# alphanewt_v0_3.net
KiCad netlist of a schematic drawn in EAGLE
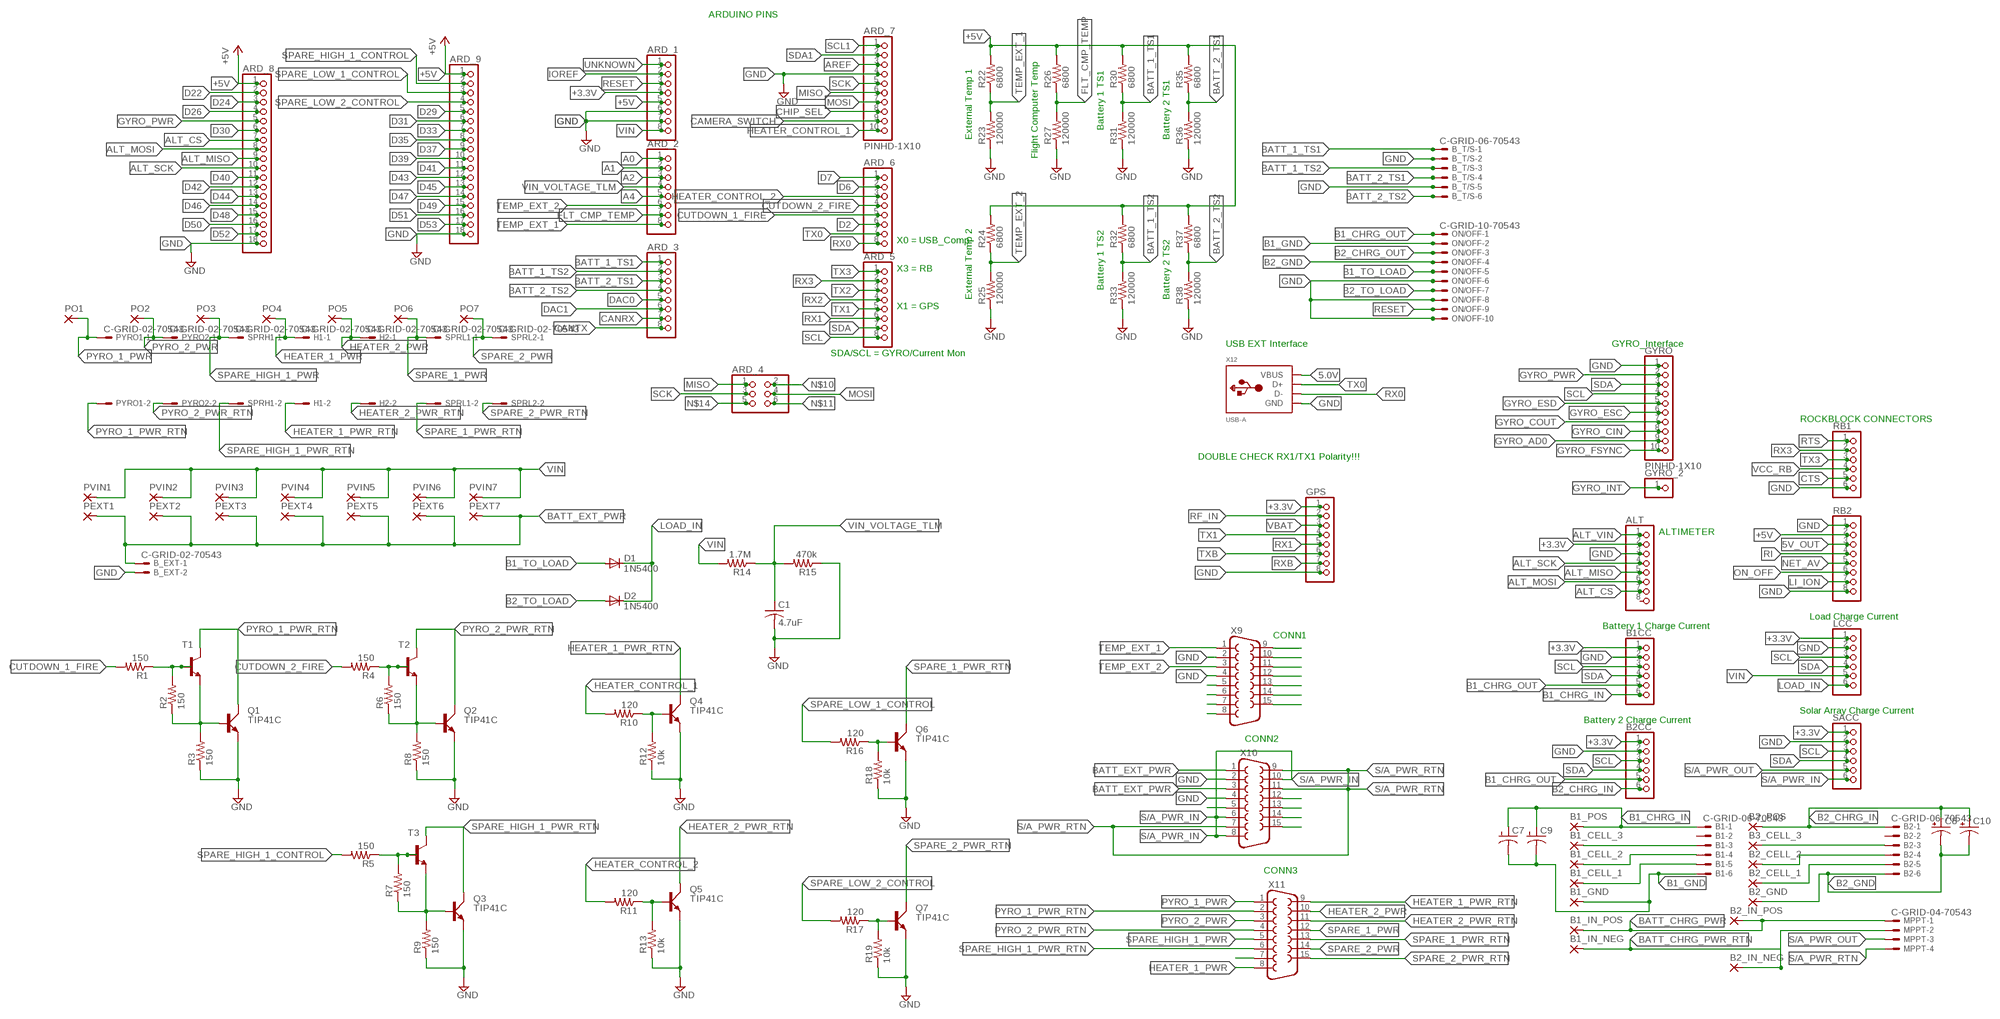
[diagram p0: schematic, sheet 1]

(export (version "E")
  (design (tool "Eeschema 10.0.6"))
  (components
    (comp (ref "ALT")
      (value "PINHD-1X8BIG")
      (footprint "eagle-import:1X08-BIG")
      (libsource (lib "eagle-import") (part "PINHD-1X8BIG"))
    )
    (comp (ref "ARD_1")
      (value "PINHD-1X8BIG")
      (footprint "eagle-import:1X08-BIG")
      (libsource (lib "eagle-import") (part "PINHD-1X8BIG"))
    )
    (comp (ref "ARD_2")
      (value "PINHD-1X8BIG")
      (footprint "eagle-import:1X08-BIG")
      (libsource (lib "eagle-import") (part "PINHD-1X8BIG"))
    )
    (comp (ref "ARD_3")
      (value "PINHD-1X8BIG")
      (footprint "eagle-import:1X08-BIG")
      (libsource (lib "eagle-import") (part "PINHD-1X8BIG"))
    )
    (comp (ref "ARD_4")
      (value "PINHD-2X3")
      (footprint "eagle-import:2X03")
      (libsource (lib "eagle-import") (part "PINHD-2X3"))
    )
    (comp (ref "ARD_5")
      (value "PINHD-1X8BIG")
      (footprint "eagle-import:1X08-BIG")
      (libsource (lib "eagle-import") (part "PINHD-1X8BIG"))
    )
    (comp (ref "ARD_6")
      (value "PINHD-1X8BIG")
      (footprint "eagle-import:1X08-BIG")
      (libsource (lib "eagle-import") (part "PINHD-1X8BIG"))
    )
    (comp (ref "ARD_7")
      (value "PINHD-1X10")
      (footprint "eagle-import:1X10-BIG")
      (libsource (lib "eagle-import") (part "PINHD-1X10"))
    )
    (comp (ref "ARD_8")
      (value "PINHD-1X18-BIG")
      (footprint "eagle-import:1X18-BIG")
      (libsource (lib "eagle-import") (part "PINHD-1X18-BIG"))
    )
    (comp (ref "ARD_9")
      (value "PINHD-1X18-BIG")
      (footprint "eagle-import:1X18-BIG")
      (libsource (lib "eagle-import") (part "PINHD-1X18-BIG"))
    )
    (comp (ref "B1")
      (value "C-GRID-06-70543")
      (footprint "eagle-import:70543-06")
      (libsource (lib "eagle-import") (part "C-GRID-06-70543"))
    )
    (comp (ref "B1CC")
      (value "PINHD-1X6B")
      (footprint "eagle-import:1X06-BIG")
      (libsource (lib "eagle-import") (part "PINHD-1X6B"))
    )
    (comp (ref "B1_CELL_1")
      (value "SMD5")
      (footprint "eagle-import:SMD2,54-5,08")
      (libsource (lib "eagle-import") (part "SMD5"))
    )
    (comp (ref "B1_CELL_2")
      (value "SMD5")
      (footprint "eagle-import:SMD2,54-5,08")
      (libsource (lib "eagle-import") (part "SMD5"))
    )
    (comp (ref "B1_CELL_3")
      (value "SMD5")
      (footprint "eagle-import:SMD2,54-5,08")
      (libsource (lib "eagle-import") (part "SMD5"))
    )
    (comp (ref "B1_GND")
      (value "SMD5")
      (footprint "eagle-import:SMD2,54-5,08")
      (libsource (lib "eagle-import") (part "SMD5"))
    )
    (comp (ref "B1_IN_NEG")
      (value "SMD5")
      (footprint "eagle-import:SMD2,54-5,08")
      (libsource (lib "eagle-import") (part "SMD5"))
    )
    (comp (ref "B1_IN_POS")
      (value "SMD5")
      (footprint "eagle-import:SMD2,54-5,08")
      (libsource (lib "eagle-import") (part "SMD5"))
    )
    (comp (ref "B1_POS")
      (value "SMD5")
      (footprint "eagle-import:SMD2,54-5,08")
      (libsource (lib "eagle-import") (part "SMD5"))
    )
    (comp (ref "B2")
      (value "C-GRID-06-70543")
      (footprint "eagle-import:70543-06")
      (libsource (lib "eagle-import") (part "C-GRID-06-70543"))
    )
    (comp (ref "B2CC")
      (value "PINHD-1X6B")
      (footprint "eagle-import:1X06-BIG")
      (libsource (lib "eagle-import") (part "PINHD-1X6B"))
    )
    (comp (ref "B2_CELL_1")
      (value "SMD5")
      (footprint "eagle-import:SMD2,54-5,08")
      (libsource (lib "eagle-import") (part "SMD5"))
    )
    (comp (ref "B2_CELL_2")
      (value "SMD5")
      (footprint "eagle-import:SMD2,54-5,08")
      (libsource (lib "eagle-import") (part "SMD5"))
    )
    (comp (ref "B2_GND")
      (value "SMD5")
      (footprint "eagle-import:SMD2,54-5,08")
      (libsource (lib "eagle-import") (part "SMD5"))
    )
    (comp (ref "B2_IN_NEG")
      (value "SMD5")
      (footprint "eagle-import:SMD2,54-5,08")
      (libsource (lib "eagle-import") (part "SMD5"))
    )
    (comp (ref "B2_IN_POS")
      (value "SMD5")
      (footprint "eagle-import:SMD2,54-5,08")
      (libsource (lib "eagle-import") (part "SMD5"))
    )
    (comp (ref "B2_POS")
      (value "SMD5")
      (footprint "eagle-import:SMD2,54-5,08")
      (libsource (lib "eagle-import") (part "SMD5"))
    )
    (comp (ref "B3_CELL_3")
      (value "SMD5")
      (footprint "eagle-import:SMD2,54-5,08")
      (libsource (lib "eagle-import") (part "SMD5"))
    )
    (comp (ref "B_EXT")
      (value "C-GRID-02-70543")
      (footprint "eagle-import:70543-02")
      (libsource (lib "eagle-import") (part "C-GRID-02-70543"))
    )
    (comp (ref "B_T/S")
      (value "C-GRID-06-70543")
      (footprint "eagle-import:70543-06")
      (libsource (lib "eagle-import") (part "C-GRID-06-70543"))
    )
    (comp (ref "C1")
      (value "4.7uF")
      (footprint "eagle-import:C0805K")
      (fields (field (name "MPN") "C0805C270J5GACTU"))
      (libsource (lib "eagle-import") (part "C-USC0805K"))
    )
    (comp (ref "C7")
      (value "CPOL-USCT7343")
      (footprint "eagle-import:CT7343")
      (libsource (lib "eagle-import") (part "CPOL-USCT7343"))
    )
    (comp (ref "C8")
      (value "CPOL-USCT7343")
      (footprint "eagle-import:CT7343")
      (libsource (lib "eagle-import") (part "CPOL-USCT7343"))
    )
    (comp (ref "C9")
      (value "CPOL-USCT7343")
      (footprint "eagle-import:CT7343")
      (libsource (lib "eagle-import") (part "CPOL-USCT7343"))
    )
    (comp (ref "C10")
      (value "CPOL-USCT7343")
      (footprint "eagle-import:CT7343")
      (libsource (lib "eagle-import") (part "CPOL-USCT7343"))
    )
    (comp (ref "D1")
      (value "1N5400")
      (footprint "eagle-import:DO201-15")
      (libsource (lib "eagle-import") (part "1N5400"))
    )
    (comp (ref "D2")
      (value "1N5400")
      (footprint "eagle-import:DO201-15")
      (libsource (lib "eagle-import") (part "1N5400"))
    )
    (comp (ref "GPS")
      (value "PINHD-1X8BIG")
      (footprint "eagle-import:1X08-BIG")
      (libsource (lib "eagle-import") (part "PINHD-1X8BIG"))
    )
    (comp (ref "GYRO")
      (value "PINHD-1X10")
      (footprint "eagle-import:1X10-BIG")
      (libsource (lib "eagle-import") (part "PINHD-1X10"))
    )
    (comp (ref "GYRO_2")
      (value "PINHD-1X1")
      (footprint "eagle-import:1X01")
      (libsource (lib "eagle-import") (part "PINHD-1X1"))
    )
    (comp (ref "H1")
      (value "C-GRID-02-70543")
      (footprint "eagle-import:70543-02")
      (libsource (lib "eagle-import") (part "C-GRID-02-70543"))
    )
    (comp (ref "H2")
      (value "C-GRID-02-70543")
      (footprint "eagle-import:70543-02")
      (libsource (lib "eagle-import") (part "C-GRID-02-70543"))
    )
    (comp (ref "LCC")
      (value "PINHD-1X6B")
      (footprint "eagle-import:1X06-BIG")
      (libsource (lib "eagle-import") (part "PINHD-1X6B"))
    )
    (comp (ref "MPPT")
      (value "C-GRID-04-70543")
      (footprint "eagle-import:70543-04")
      (libsource (lib "eagle-import") (part "C-GRID-04-70543"))
    )
    (comp (ref "ON/OFF")
      (value "C-GRID-10-70543")
      (footprint "eagle-import:70543-10")
      (libsource (lib "eagle-import") (part "C-GRID-10-70543"))
    )
    (comp (ref "PEXT1")
      (value "SMD2")
      (footprint "eagle-import:SMD1,27-2,54")
      (libsource (lib "eagle-import") (part "SMD2"))
    )
    (comp (ref "PEXT2")
      (value "SMD2")
      (footprint "eagle-import:SMD1,27-2,54")
      (libsource (lib "eagle-import") (part "SMD2"))
    )
    (comp (ref "PEXT3")
      (value "SMD2")
      (footprint "eagle-import:SMD1,27-2,54")
      (libsource (lib "eagle-import") (part "SMD2"))
    )
    (comp (ref "PEXT4")
      (value "SMD2")
      (footprint "eagle-import:SMD1,27-2,54")
      (libsource (lib "eagle-import") (part "SMD2"))
    )
    (comp (ref "PEXT5")
      (value "SMD2")
      (footprint "eagle-import:SMD1,27-2,54")
      (libsource (lib "eagle-import") (part "SMD2"))
    )
    (comp (ref "PEXT6")
      (value "SMD2")
      (footprint "eagle-import:SMD1,27-2,54")
      (libsource (lib "eagle-import") (part "SMD2"))
    )
    (comp (ref "PEXT7")
      (value "SMD2")
      (footprint "eagle-import:SMD1,27-2,54")
      (libsource (lib "eagle-import") (part "SMD2"))
    )
    (comp (ref "PO1")
      (value "SMD2")
      (footprint "eagle-import:SMD1,27-2,54")
      (libsource (lib "eagle-import") (part "SMD2"))
    )
    (comp (ref "PO2")
      (value "SMD2")
      (footprint "eagle-import:SMD1,27-2,54")
      (libsource (lib "eagle-import") (part "SMD2"))
    )
    (comp (ref "PO3")
      (value "SMD2")
      (footprint "eagle-import:SMD1,27-2,54")
      (libsource (lib "eagle-import") (part "SMD2"))
    )
    (comp (ref "PO4")
      (value "SMD2")
      (footprint "eagle-import:SMD1,27-2,54")
      (libsource (lib "eagle-import") (part "SMD2"))
    )
    (comp (ref "PO5")
      (value "SMD2")
      (footprint "eagle-import:SMD1,27-2,54")
      (libsource (lib "eagle-import") (part "SMD2"))
    )
    (comp (ref "PO6")
      (value "SMD2")
      (footprint "eagle-import:SMD1,27-2,54")
      (libsource (lib "eagle-import") (part "SMD2"))
    )
    (comp (ref "PO7")
      (value "SMD2")
      (footprint "eagle-import:SMD1,27-2,54")
      (libsource (lib "eagle-import") (part "SMD2"))
    )
    (comp (ref "PVIN1")
      (value "SMD2")
      (footprint "eagle-import:SMD1,27-2,54")
      (libsource (lib "eagle-import") (part "SMD2"))
    )
    (comp (ref "PVIN2")
      (value "SMD2")
      (footprint "eagle-import:SMD1,27-2,54")
      (libsource (lib "eagle-import") (part "SMD2"))
    )
    (comp (ref "PVIN3")
      (value "SMD2")
      (footprint "eagle-import:SMD1,27-2,54")
      (libsource (lib "eagle-import") (part "SMD2"))
    )
    (comp (ref "PVIN4")
      (value "SMD2")
      (footprint "eagle-import:SMD1,27-2,54")
      (libsource (lib "eagle-import") (part "SMD2"))
    )
    (comp (ref "PVIN5")
      (value "SMD2")
      (footprint "eagle-import:SMD1,27-2,54")
      (libsource (lib "eagle-import") (part "SMD2"))
    )
    (comp (ref "PVIN6")
      (value "SMD2")
      (footprint "eagle-import:SMD1,27-2,54")
      (libsource (lib "eagle-import") (part "SMD2"))
    )
    (comp (ref "PVIN7")
      (value "SMD2")
      (footprint "eagle-import:SMD1,27-2,54")
      (libsource (lib "eagle-import") (part "SMD2"))
    )
    (comp (ref "PYRO1")
      (value "C-GRID-02-70543")
      (footprint "eagle-import:70543-02")
      (libsource (lib "eagle-import") (part "C-GRID-02-70543"))
    )
    (comp (ref "PYRO2")
      (value "C-GRID-02-70543")
      (footprint "eagle-import:70543-02")
      (libsource (lib "eagle-import") (part "C-GRID-02-70543"))
    )
    (comp (ref "Q1")
      (value "TIP41C")
      (footprint "eagle-import:TO220AV")
      (libsource (lib "eagle-import") (part "TIP41C"))
    )
    (comp (ref "Q2")
      (value "TIP41C")
      (footprint "eagle-import:TO220AV")
      (libsource (lib "eagle-import") (part "TIP41C"))
    )
    (comp (ref "Q3")
      (value "TIP41C")
      (footprint "eagle-import:TO220AV")
      (libsource (lib "eagle-import") (part "TIP41C"))
    )
    (comp (ref "Q4")
      (value "TIP41C")
      (footprint "eagle-import:TO220AV")
      (libsource (lib "eagle-import") (part "TIP41C"))
    )
    (comp (ref "Q5")
      (value "TIP41C")
      (footprint "eagle-import:TO220AV")
      (libsource (lib "eagle-import") (part "TIP41C"))
    )
    (comp (ref "Q6")
      (value "TIP41C")
      (footprint "eagle-import:TO220AV")
      (libsource (lib "eagle-import") (part "TIP41C"))
    )
    (comp (ref "Q7")
      (value "TIP41C")
      (footprint "eagle-import:TO220AV")
      (libsource (lib "eagle-import") (part "TIP41C"))
    )
    (comp (ref "R1")
      (value "150")
      (footprint "eagle-import:R0805")
      (fields (field (name "MF") "VISHAY/DALE") (field (name "MPN") "CRCW120633R2FKEA"))
      (libsource (lib "eagle-import") (part "R-US_R0805"))
    )
    (comp (ref "R2")
      (value "150")
      (footprint "eagle-import:R0805")
      (fields (field (name "MF") "VISHAY/DALE") (field (name "MPN") "CRCW120633R2FKEA"))
      (libsource (lib "eagle-import") (part "R-US_R0805"))
    )
    (comp (ref "R3")
      (value "150")
      (footprint "eagle-import:R0805")
      (fields (field (name "MF") "VISHAY/DALE") (field (name "MPN") "CRCW120633R2FKEA"))
      (libsource (lib "eagle-import") (part "R-US_R0805"))
    )
    (comp (ref "R4")
      (value "150")
      (footprint "eagle-import:R0805")
      (fields (field (name "MF") "VISHAY/DALE") (field (name "MPN") "CRCW120633R2FKEA"))
      (libsource (lib "eagle-import") (part "R-US_R0805"))
    )
    (comp (ref "R5")
      (value "150")
      (footprint "eagle-import:R0805")
      (fields (field (name "MF") "VISHAY/DALE") (field (name "MPN") "CRCW120633R2FKEA"))
      (libsource (lib "eagle-import") (part "R-US_R0805"))
    )
    (comp (ref "R6")
      (value "150")
      (footprint "eagle-import:R0805")
      (fields (field (name "MF") "VISHAY/DALE") (field (name "MPN") "CRCW120633R2FKEA"))
      (libsource (lib "eagle-import") (part "R-US_R0805"))
    )
    (comp (ref "R7")
      (value "150")
      (footprint "eagle-import:R0805")
      (fields (field (name "MF") "VISHAY/DALE") (field (name "MPN") "CRCW120633R2FKEA"))
      (libsource (lib "eagle-import") (part "R-US_R0805"))
    )
    (comp (ref "R8")
      (value "150")
      (footprint "eagle-import:R0805")
      (fields (field (name "MF") "VISHAY/DALE") (field (name "MPN") "CRCW120633R2FKEA"))
      (libsource (lib "eagle-import") (part "R-US_R0805"))
    )
    (comp (ref "R9")
      (value "150")
      (footprint "eagle-import:R0805")
      (fields (field (name "MF") "VISHAY/DALE") (field (name "MPN") "CRCW120633R2FKEA"))
      (libsource (lib "eagle-import") (part "R-US_R0805"))
    )
    (comp (ref "R10")
      (value "120")
      (footprint "eagle-import:R0805")
      (fields (field (name "MF") "VISHAY/DALE") (field (name "MPN") "CRCW120633R2FKEA"))
      (libsource (lib "eagle-import") (part "R-US_R0805"))
    )
    (comp (ref "R11")
      (value "120")
      (footprint "eagle-import:R0805")
      (fields (field (name "MF") "VISHAY/DALE") (field (name "MPN") "CRCW120633R2FKEA"))
      (libsource (lib "eagle-import") (part "R-US_R0805"))
    )
    (comp (ref "R12")
      (value "10k")
      (footprint "eagle-import:R0805")
      (fields (field (name "MF") "VISHAY/DALE") (field (name "MPN") "CRCW120633R2FKEA"))
      (libsource (lib "eagle-import") (part "R-US_R0805"))
    )
    (comp (ref "R13")
      (value "10k")
      (footprint "eagle-import:R0805")
      (fields (field (name "MF") "VISHAY/DALE") (field (name "MPN") "CRCW120633R2FKEA"))
      (libsource (lib "eagle-import") (part "R-US_R0805"))
    )
    (comp (ref "R14")
      (value "1.7M")
      (footprint "eagle-import:R0805")
      (fields (field (name "MF") "VISHAY/DALE") (field (name "MPN") "CRCW120633R2FKEA"))
      (libsource (lib "eagle-import") (part "R-US_R0805"))
    )
    (comp (ref "R15")
      (value "470k")
      (footprint "eagle-import:R0805")
      (fields (field (name "MF") "VISHAY/DALE") (field (name "MPN") "CRCW120633R2FKEA"))
      (libsource (lib "eagle-import") (part "R-US_R0805"))
    )
    (comp (ref "R16")
      (value "120")
      (footprint "eagle-import:R0805")
      (fields (field (name "MF") "VISHAY/DALE") (field (name "MPN") "CRCW120633R2FKEA"))
      (libsource (lib "eagle-import") (part "R-US_R0805"))
    )
    (comp (ref "R17")
      (value "120")
      (footprint "eagle-import:R0805")
      (fields (field (name "MF") "VISHAY/DALE") (field (name "MPN") "CRCW120633R2FKEA"))
      (libsource (lib "eagle-import") (part "R-US_R0805"))
    )
    (comp (ref "R18")
      (value "10k")
      (footprint "eagle-import:R0805")
      (fields (field (name "MF") "VISHAY/DALE") (field (name "MPN") "CRCW120633R2FKEA"))
      (libsource (lib "eagle-import") (part "R-US_R0805"))
    )
    (comp (ref "R19")
      (value "10k")
      (footprint "eagle-import:R0805")
      (fields (field (name "MF") "VISHAY/DALE") (field (name "MPN") "CRCW120633R2FKEA"))
      (libsource (lib "eagle-import") (part "R-US_R0805"))
    )
    (comp (ref "R22")
      (value "6800")
      (footprint "eagle-import:R0805")
      (fields (field (name "MF") "VISHAY/DALE") (field (name "MPN") "CRCW120633R2FKEA"))
      (libsource (lib "eagle-import") (part "R-US_R0805"))
    )
    (comp (ref "R23")
      (value "120000")
      (footprint "eagle-import:R0805")
      (fields (field (name "MF") "VISHAY/DALE") (field (name "MPN") "CRCW120633R2FKEA"))
      (libsource (lib "eagle-import") (part "R-US_R0805"))
    )
    (comp (ref "R24")
      (value "6800")
      (footprint "eagle-import:R0805")
      (fields (field (name "MF") "VISHAY/DALE") (field (name "MPN") "CRCW120633R2FKEA"))
      (libsource (lib "eagle-import") (part "R-US_R0805"))
    )
    (comp (ref "R25")
      (value "120000")
      (footprint "eagle-import:R0805")
      (fields (field (name "MF") "VISHAY/DALE") (field (name "MPN") "CRCW120633R2FKEA"))
      (libsource (lib "eagle-import") (part "R-US_R0805"))
    )
    (comp (ref "R26")
      (value "6800")
      (footprint "eagle-import:R0805")
      (fields (field (name "MF") "VISHAY/DALE") (field (name "MPN") "CRCW120633R2FKEA"))
      (libsource (lib "eagle-import") (part "R-US_R0805"))
    )
    (comp (ref "R27")
      (value "120000")
      (footprint "eagle-import:R0805")
      (fields (field (name "MF") "VISHAY/DALE") (field (name "MPN") "CRCW120633R2FKEA"))
      (libsource (lib "eagle-import") (part "R-US_R0805"))
    )
    (comp (ref "R30")
      (value "6800")
      (footprint "eagle-import:R0805")
      (fields (field (name "MF") "VISHAY/DALE") (field (name "MPN") "CRCW120633R2FKEA"))
      (libsource (lib "eagle-import") (part "R-US_R0805"))
    )
    (comp (ref "R31")
      (value "120000")
      (footprint "eagle-import:R0805")
      (fields (field (name "MF") "VISHAY/DALE") (field (name "MPN") "CRCW120633R2FKEA"))
      (libsource (lib "eagle-import") (part "R-US_R0805"))
    )
    (comp (ref "R32")
      (value "6800")
      (footprint "eagle-import:R0805")
      (fields (field (name "MF") "VISHAY/DALE") (field (name "MPN") "CRCW120633R2FKEA"))
      (libsource (lib "eagle-import") (part "R-US_R0805"))
    )
    (comp (ref "R33")
      (value "120000")
      (footprint "eagle-import:R0805")
      (fields (field (name "MF") "VISHAY/DALE") (field (name "MPN") "CRCW120633R2FKEA"))
      (libsource (lib "eagle-import") (part "R-US_R0805"))
    )
    (comp (ref "R35")
      (value "6800")
      (footprint "eagle-import:R0805")
      (fields (field (name "MF") "VISHAY/DALE") (field (name "MPN") "CRCW120633R2FKEA"))
      (libsource (lib "eagle-import") (part "R-US_R0805"))
    )
    (comp (ref "R36")
      (value "120000")
      (footprint "eagle-import:R0805")
      (fields (field (name "MF") "VISHAY/DALE") (field (name "MPN") "CRCW120633R2FKEA"))
      (libsource (lib "eagle-import") (part "R-US_R0805"))
    )
    (comp (ref "R37")
      (value "6800")
      (footprint "eagle-import:R0805")
      (fields (field (name "MF") "VISHAY/DALE") (field (name "MPN") "CRCW120633R2FKEA"))
      (libsource (lib "eagle-import") (part "R-US_R0805"))
    )
    (comp (ref "R38")
      (value "120000")
      (footprint "eagle-import:R0805")
      (fields (field (name "MF") "VISHAY/DALE") (field (name "MPN") "CRCW120633R2FKEA"))
      (libsource (lib "eagle-import") (part "R-US_R0805"))
    )
    (comp (ref "RB1")
      (value "PINHD-1X6CB")
      (footprint "eagle-import:1X06-CLEANBIG")
      (libsource (lib "eagle-import") (part "PINHD-1X6CB"))
    )
    (comp (ref "RB2")
      (value "PINHD-1X8BIG")
      (footprint "eagle-import:1X08-BIG")
      (libsource (lib "eagle-import") (part "PINHD-1X8BIG"))
    )
    (comp (ref "SACC")
      (value "PINHD-1X6B")
      (footprint "eagle-import:1X06-BIG")
      (libsource (lib "eagle-import") (part "PINHD-1X6B"))
    )
    (comp (ref "SPRH1")
      (value "C-GRID-02-70543")
      (footprint "eagle-import:70543-02")
      (libsource (lib "eagle-import") (part "C-GRID-02-70543"))
    )
    (comp (ref "SPRL1")
      (value "C-GRID-02-70543")
      (footprint "eagle-import:70543-02")
      (libsource (lib "eagle-import") (part "C-GRID-02-70543"))
    )
    (comp (ref "SPRL2")
      (value "C-GRID-02-70543")
      (footprint "eagle-import:70543-02")
      (libsource (lib "eagle-import") (part "C-GRID-02-70543"))
    )
    (comp (ref "T1")
      (value "2N3904")
      (footprint "eagle-import:TO92")
      (libsource (lib "eagle-import") (part "2N3904"))
    )
    (comp (ref "T2")
      (value "2N3904")
      (footprint "eagle-import:TO92")
      (libsource (lib "eagle-import") (part "2N3904"))
    )
    (comp (ref "T3")
      (value "2N3904")
      (footprint "eagle-import:TO92")
      (libsource (lib "eagle-import") (part "2N3904"))
    )
    (comp (ref "X9")
      (value "F15HP")
      (footprint "eagle-import:F15HP")
      (libsource (lib "eagle-import") (part "F15HP"))
    )
    (comp (ref "X10")
      (value "F15HP")
      (footprint "eagle-import:F15HP")
      (libsource (lib "eagle-import") (part "F15HP"))
    )
    (comp (ref "X11")
      (value "F15HP")
      (footprint "eagle-import:F15HP")
      (libsource (lib "eagle-import") (part "F15HP"))
    )
    (comp (ref "X12")
      (value "USB-A")
      (footprint "eagle-import:MOLEX_480371000")
      (libsource (lib "eagle-import") (part "USB-A"))
    )
  )
  (nets
    (net (code "1") (name "+3.3V") (class "Default")
      (node (ref "ALT") (pin "2") (pinfunction "2_2") (pintype "passive"))
      (node (ref "ARD_1") (pin "4") (pinfunction "4_4") (pintype "passive"))
      (node (ref "B1CC") (pin "1") (pinfunction "1_1") (pintype "passive"))
      (node (ref "B2CC") (pin "1") (pinfunction "1_1") (pintype "passive"))
      (node (ref "GPS") (pin "1") (pinfunction "1_1") (pintype "passive"))
      (node (ref "LCC") (pin "1") (pinfunction "1_1") (pintype "passive"))
      (node (ref "SACC") (pin "1") (pinfunction "1_1") (pintype "passive"))
    )
    (net (code "2") (name "+5V") (class "Default")
      (node (ref "ARD_1") (pin "5") (pinfunction "5_5") (pintype "passive"))
      (node (ref "ARD_8") (pin "1") (pinfunction "1_1") (pintype "passive"))
      (node (ref "ARD_9") (pin "1") (pinfunction "1_1") (pintype "passive"))
      (node (ref "R22") (pin "2") (pinfunction "2_2") (pintype "passive"))
      (node (ref "R24") (pin "2") (pinfunction "2_2") (pintype "passive"))
      (node (ref "R26") (pin "2") (pinfunction "2_2") (pintype "passive"))
      (node (ref "R30") (pin "2") (pinfunction "2_2") (pintype "passive"))
      (node (ref "R32") (pin "2") (pinfunction "2_2") (pintype "passive"))
      (node (ref "R35") (pin "2") (pinfunction "2_2") (pintype "passive"))
      (node (ref "R37") (pin "2") (pinfunction "2_2") (pintype "passive"))
      (node (ref "RB2") (pin "2") (pinfunction "2_2") (pintype "passive"))
    )
    (net (code "3") (name "5.0V") (class "Default")
      (node (ref "X12") (pin "1") (pinfunction "VBUS_1") (pintype "power_in"))
    )
    (net (code "4") (name "5V_OUT") (class "Default")
      (node (ref "RB2") (pin "3") (pinfunction "3_3") (pintype "passive"))
    )
    (net (code "5") (name "A0") (class "Default")
      (node (ref "ARD_2") (pin "1") (pinfunction "1_1") (pintype "passive"))
    )
    (net (code "6") (name "A1") (class "Default")
      (node (ref "ARD_2") (pin "2") (pinfunction "2_2") (pintype "passive"))
    )
    (net (code "7") (name "A2") (class "Default")
      (node (ref "ARD_2") (pin "3") (pinfunction "3_3") (pintype "passive"))
    )
    (net (code "8") (name "A4") (class "Default")
      (node (ref "ARD_2") (pin "5") (pinfunction "5_5") (pintype "passive"))
    )
    (net (code "9") (name "ALT_CS") (class "Default")
      (node (ref "ALT") (pin "7") (pinfunction "7_7") (pintype "passive"))
      (node (ref "ARD_8") (pin "7") (pinfunction "7_7") (pintype "passive"))
    )
    (net (code "10") (name "ALT_MISO") (class "Default")
      (node (ref "ALT") (pin "5") (pinfunction "5_5") (pintype "passive"))
      (node (ref "ARD_8") (pin "9") (pinfunction "9_9") (pintype "passive"))
    )
    (net (code "11") (name "ALT_MOSI") (class "Default")
      (node (ref "ALT") (pin "6") (pinfunction "6_6") (pintype "passive"))
      (node (ref "ARD_8") (pin "8") (pinfunction "8_8") (pintype "passive"))
    )
    (net (code "12") (name "ALT_SCK") (class "Default")
      (node (ref "ALT") (pin "4") (pinfunction "4_4") (pintype "passive"))
      (node (ref "ARD_8") (pin "10") (pinfunction "10_10") (pintype "passive"))
    )
    (net (code "13") (name "ALT_VIN") (class "Default")
      (node (ref "ALT") (pin "1") (pinfunction "1_1") (pintype "passive"))
    )
    (net (code "14") (name "AREF") (class "Default")
      (node (ref "ARD_7") (pin "3") (pinfunction "3_3") (pintype "passive"))
    )
    (net (code "15") (name "B1_CHRG_IN") (class "Default")
      (node (ref "B1") (pin "1") (pinfunction "S_1") (pintype "passive"))
      (node (ref "B1CC") (pin "6") (pinfunction "6_6") (pintype "passive"))
      (node (ref "B1_POS") (pin "1") (pinfunction "P_1") (pintype "passive"))
      (node (ref "C7") (pin "+") (pinfunction "+_+") (pintype "passive"))
      (node (ref "C9") (pin "+") (pinfunction "+_+") (pintype "passive"))
    )
    (net (code "16") (name "B1_CHRG_OUT") (class "Default")
      (node (ref "B1CC") (pin "5") (pinfunction "5_5") (pintype "passive"))
      (node (ref "B2CC") (pin "5") (pinfunction "5_5") (pintype "passive"))
      (node (ref "ON/OFF") (pin "1") (pinfunction "S_1") (pintype "passive"))
    )
    (net (code "17") (name "B1_GND") (class "Default")
      (node (ref "B1") (pin "6") (pinfunction "S_6") (pintype "passive"))
      (node (ref "B1_GND") (pin "1") (pinfunction "P_1") (pintype "passive"))
      (node (ref "C7") (pin "-") (pinfunction "-_-") (pintype "passive"))
      (node (ref "C9") (pin "-") (pinfunction "-_-") (pintype "passive"))
      (node (ref "ON/OFF") (pin "2") (pinfunction "S_2") (pintype "passive"))
    )
    (net (code "18") (name "B1_TO_LOAD") (class "Default")
      (node (ref "D1") (pin "A") (pinfunction "A_A") (pintype "passive"))
      (node (ref "ON/OFF") (pin "5") (pinfunction "S_5") (pintype "passive"))
    )
    (net (code "19") (name "B2_CHRG_IN") (class "Default")
      (node (ref "B2") (pin "1") (pinfunction "S_1") (pintype "passive"))
      (node (ref "B2CC") (pin "6") (pinfunction "6_6") (pintype "passive"))
      (node (ref "B2_POS") (pin "1") (pinfunction "P_1") (pintype "passive"))
      (node (ref "C10") (pin "+") (pinfunction "+_+") (pintype "passive"))
      (node (ref "C8") (pin "+") (pinfunction "+_+") (pintype "passive"))
    )
    (net (code "20") (name "B2_CHRG_OUT") (class "Default")
      (node (ref "ON/OFF") (pin "3") (pinfunction "S_3") (pintype "passive"))
    )
    (net (code "21") (name "B2_GND") (class "Default")
      (node (ref "B2") (pin "6") (pinfunction "S_6") (pintype "passive"))
      (node (ref "B2_GND") (pin "1") (pinfunction "P_1") (pintype "passive"))
      (node (ref "C10") (pin "-") (pinfunction "-_-") (pintype "passive"))
      (node (ref "C8") (pin "-") (pinfunction "-_-") (pintype "passive"))
      (node (ref "ON/OFF") (pin "4") (pinfunction "S_4") (pintype "passive"))
    )
    (net (code "22") (name "B2_TO_LOAD") (class "Default")
      (node (ref "D2") (pin "A") (pinfunction "A_A") (pintype "passive"))
      (node (ref "ON/OFF") (pin "7") (pinfunction "S_7") (pintype "passive"))
    )
    (net (code "23") (name "BATT_1_TS1") (class "Default")
      (node (ref "ARD_3") (pin "1") (pinfunction "1_1") (pintype "passive"))
      (node (ref "B_T/S") (pin "1") (pinfunction "S_1") (pintype "passive"))
      (node (ref "R30") (pin "1") (pinfunction "1_1") (pintype "passive"))
      (node (ref "R31") (pin "2") (pinfunction "2_2") (pintype "passive"))
    )
    (net (code "24") (name "BATT_1_TS2") (class "Default")
      (node (ref "ARD_3") (pin "2") (pinfunction "2_2") (pintype "passive"))
      (node (ref "B_T/S") (pin "3") (pinfunction "S_3") (pintype "passive"))
      (node (ref "R32") (pin "1") (pinfunction "1_1") (pintype "passive"))
      (node (ref "R33") (pin "2") (pinfunction "2_2") (pintype "passive"))
    )
    (net (code "25") (name "BATT_2_TS1") (class "Default")
      (node (ref "ARD_3") (pin "3") (pinfunction "3_3") (pintype "passive"))
      (node (ref "B_T/S") (pin "4") (pinfunction "S_4") (pintype "passive"))
      (node (ref "R35") (pin "1") (pinfunction "1_1") (pintype "passive"))
      (node (ref "R36") (pin "2") (pinfunction "2_2") (pintype "passive"))
    )
    (net (code "26") (name "BATT_2_TS2") (class "Default")
      (node (ref "ARD_3") (pin "4") (pinfunction "4_4") (pintype "passive"))
      (node (ref "B_T/S") (pin "6") (pinfunction "S_6") (pintype "passive"))
      (node (ref "R37") (pin "1") (pinfunction "1_1") (pintype "passive"))
      (node (ref "R38") (pin "2") (pinfunction "2_2") (pintype "passive"))
    )
    (net (code "27") (name "BATT_CHRG_PWR") (class "Default")
      (node (ref "B1_IN_POS") (pin "1") (pinfunction "P_1") (pintype "passive"))
      (node (ref "B2_IN_POS") (pin "1") (pinfunction "P_1") (pintype "passive"))
      (node (ref "MPPT") (pin "1") (pinfunction "S_1") (pintype "passive"))
    )
    (net (code "28") (name "BATT_CHRG_PWR_RTN") (class "Default")
      (node (ref "B1_IN_NEG") (pin "1") (pinfunction "P_1") (pintype "passive"))
      (node (ref "B2_IN_NEG") (pin "1") (pinfunction "P_1") (pintype "passive"))
      (node (ref "MPPT") (pin "2") (pinfunction "S_2") (pintype "passive"))
    )
    (net (code "29") (name "BATT_EXT_PWR") (class "Default")
      (node (ref "B_EXT") (pin "1") (pinfunction "S_1") (pintype "passive"))
      (node (ref "PEXT1") (pin "1") (pinfunction "P_1") (pintype "passive"))
      (node (ref "PEXT2") (pin "1") (pinfunction "P_1") (pintype "passive"))
      (node (ref "PEXT3") (pin "1") (pinfunction "P_1") (pintype "passive"))
      (node (ref "PEXT4") (pin "1") (pinfunction "P_1") (pintype "passive"))
      (node (ref "PEXT5") (pin "1") (pinfunction "P_1") (pintype "passive"))
      (node (ref "PEXT6") (pin "1") (pinfunction "P_1") (pintype "passive"))
      (node (ref "PEXT7") (pin "1") (pinfunction "P_1") (pintype "passive"))
      (node (ref "X10") (pin "1") (pinfunction "1_1") (pintype "passive"))
      (node (ref "X10") (pin "3") (pinfunction "3_3") (pintype "passive"))
    )
    (net (code "30") (name "CAMERA_SWITCH") (class "Default")
      (node (ref "ARD_7") (pin "9") (pinfunction "9_9") (pintype "passive"))
    )
    (net (code "31") (name "CANRX") (class "Default")
      (node (ref "ARD_3") (pin "7") (pinfunction "7_7") (pintype "passive"))
    )
    (net (code "32") (name "CANTX") (class "Default")
      (node (ref "ARD_3") (pin "8") (pinfunction "8_8") (pintype "passive"))
    )
    (net (code "33") (name "CHIP_SEL") (class "Default")
      (node (ref "ARD_7") (pin "8") (pinfunction "8_8") (pintype "passive"))
    )
    (net (code "34") (name "CTS") (class "Default")
      (node (ref "RB1") (pin "5") (pinfunction "5_5") (pintype "passive"))
    )
    (net (code "35") (name "CUTDOWN_1_FIRE") (class "Default")
      (node (ref "ARD_6") (pin "5") (pinfunction "5_5") (pintype "passive"))
      (node (ref "R1") (pin "2") (pinfunction "2_2") (pintype "passive"))
    )
    (net (code "36") (name "CUTDOWN_2_FIRE") (class "Default")
      (node (ref "ARD_6") (pin "4") (pinfunction "4_4") (pintype "passive"))
      (node (ref "R4") (pin "2") (pinfunction "2_2") (pintype "passive"))
    )
    (net (code "37") (name "D2") (class "Default")
      (node (ref "ARD_6") (pin "6") (pinfunction "6_6") (pintype "passive"))
    )
    (net (code "38") (name "D6") (class "Default")
      (node (ref "ARD_6") (pin "2") (pinfunction "2_2") (pintype "passive"))
    )
    (net (code "39") (name "D7") (class "Default")
      (node (ref "ARD_6") (pin "1") (pinfunction "1_1") (pintype "passive"))
    )
    (net (code "40") (name "D22") (class "Default")
      (node (ref "ARD_8") (pin "2") (pinfunction "2_2") (pintype "passive"))
    )
    (net (code "41") (name "D24") (class "Default")
      (node (ref "ARD_8") (pin "3") (pinfunction "3_3") (pintype "passive"))
    )
    (net (code "42") (name "D26") (class "Default")
      (node (ref "ARD_8") (pin "4") (pinfunction "4_4") (pintype "passive"))
    )
    (net (code "43") (name "D29") (class "Default")
      (node (ref "ARD_9") (pin "5") (pinfunction "5_5") (pintype "passive"))
    )
    (net (code "44") (name "D30") (class "Default")
      (node (ref "ARD_8") (pin "6") (pinfunction "6_6") (pintype "passive"))
    )
    (net (code "45") (name "D31") (class "Default")
      (node (ref "ARD_9") (pin "6") (pinfunction "6_6") (pintype "passive"))
    )
    (net (code "46") (name "D33") (class "Default")
      (node (ref "ARD_9") (pin "7") (pinfunction "7_7") (pintype "passive"))
    )
    (net (code "47") (name "D35") (class "Default")
      (node (ref "ARD_9") (pin "8") (pinfunction "8_8") (pintype "passive"))
    )
    (net (code "48") (name "D37") (class "Default")
      (node (ref "ARD_9") (pin "9") (pinfunction "9_9") (pintype "passive"))
    )
    (net (code "49") (name "D39") (class "Default")
      (node (ref "ARD_9") (pin "10") (pinfunction "10_10") (pintype "passive"))
    )
    (net (code "50") (name "D40") (class "Default")
      (node (ref "ARD_8") (pin "11") (pinfunction "11_11") (pintype "passive"))
    )
    (net (code "51") (name "D41") (class "Default")
      (node (ref "ARD_9") (pin "11") (pinfunction "11_11") (pintype "passive"))
    )
    (net (code "52") (name "D42") (class "Default")
      (node (ref "ARD_8") (pin "12") (pinfunction "12_12") (pintype "passive"))
    )
    (net (code "53") (name "D43") (class "Default")
      (node (ref "ARD_9") (pin "12") (pinfunction "12_12") (pintype "passive"))
    )
    (net (code "54") (name "D44") (class "Default")
      (node (ref "ARD_8") (pin "13") (pinfunction "13_13") (pintype "passive"))
    )
    (net (code "55") (name "D45") (class "Default")
      (node (ref "ARD_9") (pin "13") (pinfunction "13_13") (pintype "passive"))
    )
    (net (code "56") (name "D46") (class "Default")
      (node (ref "ARD_8") (pin "14") (pinfunction "14_14") (pintype "passive"))
    )
    (net (code "57") (name "D47") (class "Default")
      (node (ref "ARD_9") (pin "14") (pinfunction "14_14") (pintype "passive"))
    )
    (net (code "58") (name "D48") (class "Default")
      (node (ref "ARD_8") (pin "15") (pinfunction "15_15") (pintype "passive"))
    )
    (net (code "59") (name "D49") (class "Default")
      (node (ref "ARD_9") (pin "15") (pinfunction "15_15") (pintype "passive"))
    )
    (net (code "60") (name "D50") (class "Default")
      (node (ref "ARD_8") (pin "16") (pinfunction "16_16") (pintype "passive"))
    )
    (net (code "61") (name "D51") (class "Default")
      (node (ref "ARD_9") (pin "16") (pinfunction "16_16") (pintype "passive"))
    )
    (net (code "62") (name "D52") (class "Default")
      (node (ref "ARD_8") (pin "17") (pinfunction "17_17") (pintype "passive"))
    )
    (net (code "63") (name "D53") (class "Default")
      (node (ref "ARD_9") (pin "17") (pinfunction "17_17") (pintype "passive"))
    )
    (net (code "64") (name "DAC0") (class "Default")
      (node (ref "ARD_3") (pin "5") (pinfunction "5_5") (pintype "passive"))
    )
    (net (code "65") (name "DAC1") (class "Default")
      (node (ref "ARD_3") (pin "6") (pinfunction "6_6") (pintype "passive"))
    )
    (net (code "66") (name "FLT_CMP_TEMP") (class "Default")
      (node (ref "ARD_2") (pin "7") (pinfunction "7_7") (pintype "passive"))
      (node (ref "R26") (pin "1") (pinfunction "1_1") (pintype "passive"))
      (node (ref "R27") (pin "2") (pinfunction "2_2") (pintype "passive"))
    )
    (net (code "67") (name "GND") (class "Default")
      (node (ref "ALT") (pin "3") (pinfunction "3_3") (pintype "passive"))
      (node (ref "ARD_1") (pin "6") (pinfunction "6_6") (pintype "passive"))
      (node (ref "ARD_1") (pin "7") (pinfunction "7_7") (pintype "passive"))
      (node (ref "ARD_7") (pin "4") (pinfunction "4_4") (pintype "passive"))
      (node (ref "ARD_8") (pin "18") (pinfunction "18_18") (pintype "passive"))
      (node (ref "ARD_9") (pin "18") (pinfunction "18_18") (pintype "passive"))
      (node (ref "B1CC") (pin "2") (pinfunction "2_2") (pintype "passive"))
      (node (ref "B2CC") (pin "2") (pinfunction "2_2") (pintype "passive"))
      (node (ref "B_EXT") (pin "2") (pinfunction "S_2") (pintype "passive"))
      (node (ref "B_T/S") (pin "2") (pinfunction "S_2") (pintype "passive"))
      (node (ref "B_T/S") (pin "5") (pinfunction "S_5") (pintype "passive"))
      (node (ref "C1") (pin "2") (pinfunction "2_2") (pintype "passive"))
      (node (ref "GPS") (pin "8") (pinfunction "8_8") (pintype "passive"))
      (node (ref "GYRO") (pin "1") (pinfunction "1_1") (pintype "passive"))
      (node (ref "LCC") (pin "2") (pinfunction "2_2") (pintype "passive"))
      (node (ref "ON/OFF") (pin "10") (pinfunction "S_10") (pintype "passive"))
      (node (ref "ON/OFF") (pin "6") (pinfunction "S_6") (pintype "passive"))
      (node (ref "ON/OFF") (pin "8") (pinfunction "S_8") (pintype "passive"))
      (node (ref "Q1") (pin "E") (pinfunction "E_E") (pintype "passive"))
      (node (ref "Q2") (pin "E") (pinfunction "E_E") (pintype "passive"))
      (node (ref "Q3") (pin "E") (pinfunction "E_E") (pintype "passive"))
      (node (ref "Q4") (pin "E") (pinfunction "E_E") (pintype "passive"))
      (node (ref "Q5") (pin "E") (pinfunction "E_E") (pintype "passive"))
      (node (ref "Q6") (pin "E") (pinfunction "E_E") (pintype "passive"))
      (node (ref "Q7") (pin "E") (pinfunction "E_E") (pintype "passive"))
      (node (ref "R12") (pin "1") (pinfunction "1_1") (pintype "passive"))
      (node (ref "R13") (pin "1") (pinfunction "1_1") (pintype "passive"))
      (node (ref "R15") (pin "1") (pinfunction "1_1") (pintype "passive"))
      (node (ref "R18") (pin "1") (pinfunction "1_1") (pintype "passive"))
      (node (ref "R19") (pin "1") (pinfunction "1_1") (pintype "passive"))
      (node (ref "R23") (pin "1") (pinfunction "1_1") (pintype "passive"))
      (node (ref "R25") (pin "1") (pinfunction "1_1") (pintype "passive"))
      (node (ref "R27") (pin "1") (pinfunction "1_1") (pintype "passive"))
      (node (ref "R3") (pin "1") (pinfunction "1_1") (pintype "passive"))
      (node (ref "R31") (pin "1") (pinfunction "1_1") (pintype "passive"))
      (node (ref "R33") (pin "1") (pinfunction "1_1") (pintype "passive"))
      (node (ref "R36") (pin "1") (pinfunction "1_1") (pintype "passive"))
      (node (ref "R38") (pin "1") (pinfunction "1_1") (pintype "passive"))
      (node (ref "R8") (pin "1") (pinfunction "1_1") (pintype "passive"))
      (node (ref "R9") (pin "1") (pinfunction "1_1") (pintype "passive"))
      (node (ref "RB1") (pin "6") (pinfunction "6_6") (pintype "passive"))
      (node (ref "RB2") (pin "1") (pinfunction "1_1") (pintype "passive"))
      (node (ref "RB2") (pin "8") (pinfunction "8_8") (pintype "passive"))
      (node (ref "SACC") (pin "2") (pinfunction "2_2") (pintype "passive"))
      (node (ref "X10") (pin "2") (pinfunction "2_2") (pintype "passive"))
      (node (ref "X10") (pin "4") (pinfunction "4_4") (pintype "passive"))
      (node (ref "X12") (pin "4") (pinfunction "GND_4") (pintype "power_in"))
      (node (ref "X9") (pin "2") (pinfunction "2_2") (pintype "passive"))
      (node (ref "X9") (pin "4") (pinfunction "4_4") (pintype "passive"))
    )
    (net (code "68") (name "GYRO_AD0") (class "Default")
      (node (ref "GYRO") (pin "9") (pinfunction "9_9") (pintype "passive"))
    )
    (net (code "69") (name "GYRO_CIN") (class "Default")
      (node (ref "GYRO") (pin "8") (pinfunction "8_8") (pintype "passive"))
    )
    (net (code "70") (name "GYRO_COUT") (class "Default")
      (node (ref "GYRO") (pin "7") (pinfunction "7_7") (pintype "passive"))
    )
    (net (code "71") (name "GYRO_ESC") (class "Default")
      (node (ref "GYRO") (pin "6") (pinfunction "6_6") (pintype "passive"))
    )
    (net (code "72") (name "GYRO_ESD") (class "Default")
      (node (ref "GYRO") (pin "5") (pinfunction "5_5") (pintype "passive"))
    )
    (net (code "73") (name "GYRO_FSYNC") (class "Default")
      (node (ref "GYRO") (pin "10") (pinfunction "10_10") (pintype "passive"))
    )
    (net (code "74") (name "GYRO_INT") (class "Default")
      (node (ref "GYRO_2") (pin "1") (pinfunction "1_1") (pintype "passive"))
    )
    (net (code "75") (name "GYRO_PWR") (class "Default")
      (node (ref "ARD_8") (pin "5") (pinfunction "5_5") (pintype "passive"))
      (node (ref "GYRO") (pin "2") (pinfunction "2_2") (pintype "passive"))
    )
    (net (code "76") (name "HEATER_1_PWR") (class "Default")
      (node (ref "H1") (pin "1") (pinfunction "S_1") (pintype "passive"))
      (node (ref "PO4") (pin "1") (pinfunction "P_1") (pintype "passive"))
      (node (ref "X11") (pin "8") (pinfunction "8_8") (pintype "passive"))
    )
    (net (code "77") (name "HEATER_1_PWR_RTN") (class "Default")
      (node (ref "H1") (pin "2") (pinfunction "S_2") (pintype "passive"))
      (node (ref "Q4") (pin "C") (pinfunction "C_C") (pintype "passive"))
      (node (ref "X11") (pin "9") (pinfunction "9_9") (pintype "passive"))
    )
    (net (code "78") (name "HEATER_2_PWR") (class "Default")
      (node (ref "H2") (pin "1") (pinfunction "S_1") (pintype "passive"))
      (node (ref "PO5") (pin "1") (pinfunction "P_1") (pintype "passive"))
      (node (ref "X11") (pin "10") (pinfunction "10_10") (pintype "passive"))
    )
    (net (code "79") (name "HEATER_2_PWR_RTN") (class "Default")
      (node (ref "H2") (pin "2") (pinfunction "S_2") (pintype "passive"))
      (node (ref "Q5") (pin "C") (pinfunction "C_C") (pintype "passive"))
      (node (ref "X11") (pin "11") (pinfunction "11_11") (pintype "passive"))
    )
    (net (code "80") (name "HEATER_CONTROL_1") (class "Default")
      (node (ref "ARD_7") (pin "10") (pinfunction "10_10") (pintype "passive"))
      (node (ref "R10") (pin "2") (pinfunction "2_2") (pintype "passive"))
    )
    (net (code "81") (name "HEATER_CONTROL_2") (class "Default")
      (node (ref "ARD_6") (pin "3") (pinfunction "3_3") (pintype "passive"))
      (node (ref "R11") (pin "2") (pinfunction "2_2") (pintype "passive"))
    )
    (net (code "82") (name "IOREF") (class "Default")
      (node (ref "ARD_1") (pin "2") (pinfunction "2_2") (pintype "passive"))
    )
    (net (code "83") (name "LI_ION") (class "Default")
      (node (ref "RB2") (pin "7") (pinfunction "7_7") (pintype "passive"))
    )
    (net (code "84") (name "LOAD_IN") (class "Default")
      (node (ref "D1") (pin "C") (pinfunction "C_C") (pintype "passive"))
      (node (ref "D2") (pin "C") (pinfunction "C_C") (pintype "passive"))
      (node (ref "LCC") (pin "6") (pinfunction "6_6") (pintype "passive"))
    )
    (net (code "85") (name "MISO") (class "Default")
      (node (ref "ARD_4") (pin "1") (pinfunction "1_1") (pintype "passive"))
      (node (ref "ARD_7") (pin "6") (pinfunction "6_6") (pintype "passive"))
    )
    (net (code "86") (name "MOSI") (class "Default")
      (node (ref "ARD_4") (pin "4") (pinfunction "4_4") (pintype "passive"))
      (node (ref "ARD_7") (pin "7") (pinfunction "7_7") (pintype "passive"))
    )
    (net (code "87") (name "N$10") (class "Default")
      (node (ref "ARD_4") (pin "2") (pinfunction "2_2") (pintype "passive"))
    )
    (net (code "88") (name "N$11") (class "Default")
      (node (ref "ARD_4") (pin "6") (pinfunction "6_6") (pintype "passive"))
    )
    (net (code "89") (name "N$14") (class "Default")
      (node (ref "ARD_4") (pin "5") (pinfunction "5_5") (pintype "passive"))
    )
    (net (code "90") (name "NET_AV") (class "Default")
      (node (ref "RB2") (pin "5") (pinfunction "5_5") (pintype "passive"))
    )
    (net (code "91") (name "Net-(B1C-S)") (class "Default")
      (node (ref "B1") (pin "3") (pinfunction "S_3") (pintype "passive"))
      (node (ref "B1_CELL_3") (pin "1") (pinfunction "P_1") (pintype "passive"))
    )
    (net (code "92") (name "Net-(B1D-S)") (class "Default")
      (node (ref "B1") (pin "4") (pinfunction "S_4") (pintype "passive"))
      (node (ref "B1_CELL_2") (pin "1") (pinfunction "P_1") (pintype "passive"))
    )
    (net (code "93") (name "Net-(B1E-S)") (class "Default")
      (node (ref "B1") (pin "5") (pinfunction "S_5") (pintype "passive"))
      (node (ref "B1_CELL_1") (pin "1") (pinfunction "P_1") (pintype "passive"))
    )
    (net (code "94") (name "Net-(B2C-S)") (class "Default")
      (node (ref "B2") (pin "3") (pinfunction "S_3") (pintype "passive"))
      (node (ref "B3_CELL_3") (pin "1") (pinfunction "P_1") (pintype "passive"))
    )
    (net (code "95") (name "Net-(B2D-S)") (class "Default")
      (node (ref "B2") (pin "4") (pinfunction "S_4") (pintype "passive"))
      (node (ref "B2_CELL_2") (pin "1") (pinfunction "P_1") (pintype "passive"))
    )
    (net (code "96") (name "Net-(B2E-S)") (class "Default")
      (node (ref "B2") (pin "5") (pinfunction "S_5") (pintype "passive"))
      (node (ref "B2_CELL_1") (pin "1") (pinfunction "P_1") (pintype "passive"))
    )
    (net (code "97") (name "Net-(Q4-PadB)") (class "Default")
      (node (ref "Q4") (pin "B") (pinfunction "B_B") (pintype "passive"))
      (node (ref "R10") (pin "1") (pinfunction "1_1") (pintype "passive"))
      (node (ref "R12") (pin "2") (pinfunction "2_2") (pintype "passive"))
    )
    (net (code "98") (name "Net-(Q5-PadB)") (class "Default")
      (node (ref "Q5") (pin "B") (pinfunction "B_B") (pintype "passive"))
      (node (ref "R11") (pin "1") (pinfunction "1_1") (pintype "passive"))
      (node (ref "R13") (pin "2") (pinfunction "2_2") (pintype "passive"))
    )
    (net (code "99") (name "Net-(Q6-PadB)") (class "Default")
      (node (ref "Q6") (pin "B") (pinfunction "B_B") (pintype "passive"))
      (node (ref "R16") (pin "1") (pinfunction "1_1") (pintype "passive"))
      (node (ref "R18") (pin "2") (pinfunction "2_2") (pintype "passive"))
    )
    (net (code "100") (name "Net-(Q7-PadB)") (class "Default")
      (node (ref "Q7") (pin "B") (pinfunction "B_B") (pintype "passive"))
      (node (ref "R17") (pin "1") (pinfunction "1_1") (pintype "passive"))
      (node (ref "R19") (pin "2") (pinfunction "2_2") (pintype "passive"))
    )
    (net (code "101") (name "Net-(T1-B)") (class "Default")
      (node (ref "R1") (pin "1") (pinfunction "1_1") (pintype "passive"))
      (node (ref "R2") (pin "2") (pinfunction "2_2") (pintype "passive"))
      (node (ref "T1") (pin "2") (pinfunction "B_2") (pintype "passive"))
    )
    (net (code "102") (name "Net-(T1-E)") (class "Default")
      (node (ref "Q1") (pin "B") (pinfunction "B_B") (pintype "passive"))
      (node (ref "R2") (pin "1") (pinfunction "1_1") (pintype "passive"))
      (node (ref "R3") (pin "2") (pinfunction "2_2") (pintype "passive"))
      (node (ref "T1") (pin "3") (pinfunction "E_3") (pintype "passive"))
    )
    (net (code "103") (name "Net-(T2-B)") (class "Default")
      (node (ref "R4") (pin "1") (pinfunction "1_1") (pintype "passive"))
      (node (ref "R6") (pin "2") (pinfunction "2_2") (pintype "passive"))
      (node (ref "T2") (pin "2") (pinfunction "B_2") (pintype "passive"))
    )
    (net (code "104") (name "Net-(T2-E)") (class "Default")
      (node (ref "Q2") (pin "B") (pinfunction "B_B") (pintype "passive"))
      (node (ref "R6") (pin "1") (pinfunction "1_1") (pintype "passive"))
      (node (ref "R8") (pin "2") (pinfunction "2_2") (pintype "passive"))
      (node (ref "T2") (pin "3") (pinfunction "E_3") (pintype "passive"))
    )
    (net (code "105") (name "Net-(T3-B)") (class "Default")
      (node (ref "R5") (pin "1") (pinfunction "1_1") (pintype "passive"))
      (node (ref "R7") (pin "2") (pinfunction "2_2") (pintype "passive"))
      (node (ref "T3") (pin "2") (pinfunction "B_2") (pintype "passive"))
    )
    (net (code "106") (name "Net-(T3-E)") (class "Default")
      (node (ref "Q3") (pin "B") (pinfunction "B_B") (pintype "passive"))
      (node (ref "R7") (pin "1") (pinfunction "1_1") (pintype "passive"))
      (node (ref "R9") (pin "2") (pinfunction "2_2") (pintype "passive"))
      (node (ref "T3") (pin "3") (pinfunction "E_3") (pintype "passive"))
    )
    (net (code "107") (name "ON_OFF") (class "Default")
      (node (ref "RB2") (pin "6") (pinfunction "6_6") (pintype "passive"))
    )
    (net (code "108") (name "PYRO_1_PWR") (class "Default")
      (node (ref "PO1") (pin "1") (pinfunction "P_1") (pintype "passive"))
      (node (ref "PYRO1") (pin "1") (pinfunction "S_1") (pintype "passive"))
      (node (ref "X11") (pin "1") (pinfunction "1_1") (pintype "passive"))
    )
    (net (code "109") (name "PYRO_1_PWR_RTN") (class "Default")
      (node (ref "PYRO1") (pin "2") (pinfunction "S_2") (pintype "passive"))
      (node (ref "Q1") (pin "C") (pinfunction "C_C") (pintype "passive"))
      (node (ref "T1") (pin "1") (pinfunction "C_1") (pintype "passive"))
      (node (ref "X11") (pin "2") (pinfunction "2_2") (pintype "passive"))
    )
    (net (code "110") (name "PYRO_2_PWR") (class "Default")
      (node (ref "PO2") (pin "1") (pinfunction "P_1") (pintype "passive"))
      (node (ref "PYRO2") (pin "1") (pinfunction "S_1") (pintype "passive"))
      (node (ref "X11") (pin "3") (pinfunction "3_3") (pintype "passive"))
    )
    (net (code "111") (name "PYRO_2_PWR_RTN") (class "Default")
      (node (ref "PYRO2") (pin "2") (pinfunction "S_2") (pintype "passive"))
      (node (ref "Q2") (pin "C") (pinfunction "C_C") (pintype "passive"))
      (node (ref "T2") (pin "1") (pinfunction "C_1") (pintype "passive"))
      (node (ref "X11") (pin "4") (pinfunction "4_4") (pintype "passive"))
    )
    (net (code "112") (name "RESET") (class "Default")
      (node (ref "ARD_1") (pin "3") (pinfunction "3_3") (pintype "passive"))
      (node (ref "ON/OFF") (pin "9") (pinfunction "S_9") (pintype "passive"))
    )
    (net (code "113") (name "RF_IN") (class "Default")
      (node (ref "GPS") (pin "2") (pinfunction "2_2") (pintype "passive"))
    )
    (net (code "114") (name "RI") (class "Default")
      (node (ref "RB2") (pin "4") (pinfunction "4_4") (pintype "passive"))
    )
    (net (code "115") (name "RTS") (class "Default")
      (node (ref "RB1") (pin "1") (pinfunction "1_1") (pintype "passive"))
    )
    (net (code "116") (name "RX0") (class "Default")
      (node (ref "ARD_6") (pin "8") (pinfunction "8_8") (pintype "passive"))
      (node (ref "X12") (pin "2") (pinfunction "D-_2") (pintype "bidirectional"))
    )
    (net (code "117") (name "RX1") (class "Default")
      (node (ref "ARD_5") (pin "6") (pinfunction "6_6") (pintype "passive"))
      (node (ref "GPS") (pin "5") (pinfunction "5_5") (pintype "passive"))
    )
    (net (code "118") (name "RX2") (class "Default")
      (node (ref "ARD_5") (pin "4") (pinfunction "4_4") (pintype "passive"))
    )
    (net (code "119") (name "RX3") (class "Default")
      (node (ref "ARD_5") (pin "2") (pinfunction "2_2") (pintype "passive"))
      (node (ref "RB1") (pin "2") (pinfunction "2_2") (pintype "passive"))
    )
    (net (code "120") (name "RXB") (class "Default")
      (node (ref "GPS") (pin "7") (pinfunction "7_7") (pintype "passive"))
    )
    (net (code "121") (name "SCK") (class "Default")
      (node (ref "ARD_4") (pin "3") (pinfunction "3_3") (pintype "passive"))
      (node (ref "ARD_7") (pin "5") (pinfunction "5_5") (pintype "passive"))
    )
    (net (code "122") (name "SCL") (class "Default")
      (node (ref "ARD_5") (pin "8") (pinfunction "8_8") (pintype "passive"))
      (node (ref "B1CC") (pin "3") (pinfunction "3_3") (pintype "passive"))
      (node (ref "B2CC") (pin "3") (pinfunction "3_3") (pintype "passive"))
      (node (ref "GYRO") (pin "4") (pinfunction "4_4") (pintype "passive"))
      (node (ref "LCC") (pin "3") (pinfunction "3_3") (pintype "passive"))
      (node (ref "SACC") (pin "3") (pinfunction "3_3") (pintype "passive"))
    )
    (net (code "123") (name "SCL1") (class "Default")
      (node (ref "ARD_7") (pin "1") (pinfunction "1_1") (pintype "passive"))
    )
    (net (code "124") (name "SDA") (class "Default")
      (node (ref "ARD_5") (pin "7") (pinfunction "7_7") (pintype "passive"))
      (node (ref "B1CC") (pin "4") (pinfunction "4_4") (pintype "passive"))
      (node (ref "B2CC") (pin "4") (pinfunction "4_4") (pintype "passive"))
      (node (ref "GYRO") (pin "3") (pinfunction "3_3") (pintype "passive"))
      (node (ref "LCC") (pin "4") (pinfunction "4_4") (pintype "passive"))
      (node (ref "SACC") (pin "4") (pinfunction "4_4") (pintype "passive"))
    )
    (net (code "125") (name "SDA1") (class "Default")
      (node (ref "ARD_7") (pin "2") (pinfunction "2_2") (pintype "passive"))
    )
    (net (code "126") (name "SPARE_1_PWR") (class "Default")
      (node (ref "PO6") (pin "1") (pinfunction "P_1") (pintype "passive"))
      (node (ref "SPRL1") (pin "1") (pinfunction "S_1") (pintype "passive"))
      (node (ref "X11") (pin "12") (pinfunction "12_12") (pintype "passive"))
    )
    (net (code "127") (name "SPARE_1_PWR_RTN") (class "Default")
      (node (ref "Q6") (pin "C") (pinfunction "C_C") (pintype "passive"))
      (node (ref "SPRL1") (pin "2") (pinfunction "S_2") (pintype "passive"))
      (node (ref "X11") (pin "13") (pinfunction "13_13") (pintype "passive"))
    )
    (net (code "128") (name "SPARE_2_PWR") (class "Default")
      (node (ref "PO7") (pin "1") (pinfunction "P_1") (pintype "passive"))
      (node (ref "SPRL2") (pin "1") (pinfunction "S_1") (pintype "passive"))
      (node (ref "X11") (pin "14") (pinfunction "14_14") (pintype "passive"))
    )
    (net (code "129") (name "SPARE_2_PWR_RTN") (class "Default")
      (node (ref "Q7") (pin "C") (pinfunction "C_C") (pintype "passive"))
      (node (ref "SPRL2") (pin "2") (pinfunction "S_2") (pintype "passive"))
      (node (ref "X11") (pin "15") (pinfunction "15_15") (pintype "passive"))
    )
    (net (code "130") (name "SPARE_HIGH_1_CONTROL") (class "Default")
      (node (ref "ARD_9") (pin "2") (pinfunction "2_2") (pintype "passive"))
      (node (ref "R5") (pin "2") (pinfunction "2_2") (pintype "passive"))
    )
    (net (code "131") (name "SPARE_HIGH_1_PWR") (class "Default")
      (node (ref "PO3") (pin "1") (pinfunction "P_1") (pintype "passive"))
      (node (ref "SPRH1") (pin "1") (pinfunction "S_1") (pintype "passive"))
      (node (ref "X11") (pin "5") (pinfunction "5_5") (pintype "passive"))
    )
    (net (code "132") (name "SPARE_HIGH_1_PWR_RTN") (class "Default")
      (node (ref "Q3") (pin "C") (pinfunction "C_C") (pintype "passive"))
      (node (ref "SPRH1") (pin "2") (pinfunction "S_2") (pintype "passive"))
      (node (ref "T3") (pin "1") (pinfunction "C_1") (pintype "passive"))
      (node (ref "X11") (pin "6") (pinfunction "6_6") (pintype "passive"))
    )
    (net (code "133") (name "SPARE_LOW_1_CONTROL") (class "Default")
      (node (ref "ARD_9") (pin "3") (pinfunction "3_3") (pintype "passive"))
      (node (ref "R16") (pin "2") (pinfunction "2_2") (pintype "passive"))
    )
    (net (code "134") (name "SPARE_LOW_2_CONTROL") (class "Default")
      (node (ref "ARD_9") (pin "4") (pinfunction "4_4") (pintype "passive"))
      (node (ref "R17") (pin "2") (pinfunction "2_2") (pintype "passive"))
    )
    (net (code "135") (name "S{slash}A_PWR_IN") (class "Default")
      (node (ref "SACC") (pin "6") (pinfunction "6_6") (pintype "passive"))
      (node (ref "X10") (pin "10") (pinfunction "10_10") (pintype "passive"))
      (node (ref "X10") (pin "6") (pinfunction "6_6") (pintype "passive"))
      (node (ref "X10") (pin "8") (pinfunction "8_8") (pintype "passive"))
    )
    (net (code "136") (name "S{slash}A_PWR_OUT") (class "Default")
      (node (ref "MPPT") (pin "3") (pinfunction "S_3") (pintype "passive"))
      (node (ref "SACC") (pin "5") (pinfunction "5_5") (pintype "passive"))
    )
    (net (code "137") (name "S{slash}A_PWR_RTN") (class "Default")
      (node (ref "MPPT") (pin "4") (pinfunction "S_4") (pintype "passive"))
      (node (ref "X10") (pin "11") (pinfunction "11_11") (pintype "passive"))
      (node (ref "X10") (pin "7") (pinfunction "7_7") (pintype "passive"))
      (node (ref "X10") (pin "9") (pinfunction "9_9") (pintype "passive"))
    )
    (net (code "138") (name "TEMP_EXT_1") (class "Default")
      (node (ref "ARD_2") (pin "8") (pinfunction "8_8") (pintype "passive"))
      (node (ref "R22") (pin "1") (pinfunction "1_1") (pintype "passive"))
      (node (ref "R23") (pin "2") (pinfunction "2_2") (pintype "passive"))
      (node (ref "X9") (pin "1") (pinfunction "1_1") (pintype "passive"))
    )
    (net (code "139") (name "TEMP_EXT_2") (class "Default")
      (node (ref "ARD_2") (pin "6") (pinfunction "6_6") (pintype "passive"))
      (node (ref "R24") (pin "1") (pinfunction "1_1") (pintype "passive"))
      (node (ref "R25") (pin "2") (pinfunction "2_2") (pintype "passive"))
      (node (ref "X9") (pin "3") (pinfunction "3_3") (pintype "passive"))
    )
    (net (code "140") (name "TX0") (class "Default")
      (node (ref "ARD_6") (pin "7") (pinfunction "7_7") (pintype "passive"))
      (node (ref "X12") (pin "3") (pinfunction "D+_3") (pintype "bidirectional"))
    )
    (net (code "141") (name "TX1") (class "Default")
      (node (ref "ARD_5") (pin "5") (pinfunction "5_5") (pintype "passive"))
      (node (ref "GPS") (pin "4") (pinfunction "4_4") (pintype "passive"))
    )
    (net (code "142") (name "TX2") (class "Default")
      (node (ref "ARD_5") (pin "3") (pinfunction "3_3") (pintype "passive"))
    )
    (net (code "143") (name "TX3") (class "Default")
      (node (ref "ARD_5") (pin "1") (pinfunction "1_1") (pintype "passive"))
      (node (ref "RB1") (pin "3") (pinfunction "3_3") (pintype "passive"))
    )
    (net (code "144") (name "TXB") (class "Default")
      (node (ref "GPS") (pin "6") (pinfunction "6_6") (pintype "passive"))
    )
    (net (code "145") (name "UNKNOWN") (class "Default")
      (node (ref "ARD_1") (pin "1") (pinfunction "1_1") (pintype "passive"))
    )
    (net (code "146") (name "VBAT") (class "Default")
      (node (ref "GPS") (pin "3") (pinfunction "3_3") (pintype "passive"))
    )
    (net (code "147") (name "VCC_RB") (class "Default")
      (node (ref "RB1") (pin "4") (pinfunction "4_4") (pintype "passive"))
    )
    (net (code "148") (name "VIN") (class "Default")
      (node (ref "ARD_1") (pin "8") (pinfunction "8_8") (pintype "passive"))
      (node (ref "LCC") (pin "5") (pinfunction "5_5") (pintype "passive"))
      (node (ref "PVIN1") (pin "1") (pinfunction "P_1") (pintype "passive"))
      (node (ref "PVIN2") (pin "1") (pinfunction "P_1") (pintype "passive"))
      (node (ref "PVIN3") (pin "1") (pinfunction "P_1") (pintype "passive"))
      (node (ref "PVIN4") (pin "1") (pinfunction "P_1") (pintype "passive"))
      (node (ref "PVIN5") (pin "1") (pinfunction "P_1") (pintype "passive"))
      (node (ref "PVIN6") (pin "1") (pinfunction "P_1") (pintype "passive"))
      (node (ref "PVIN7") (pin "1") (pinfunction "P_1") (pintype "passive"))
      (node (ref "R14") (pin "2") (pinfunction "2_2") (pintype "passive"))
    )
    (net (code "149") (name "VIN_VOLTAGE_TLM") (class "Default")
      (node (ref "ARD_2") (pin "4") (pinfunction "4_4") (pintype "passive"))
      (node (ref "C1") (pin "1") (pinfunction "1_1") (pintype "passive"))
      (node (ref "R14") (pin "1") (pinfunction "1_1") (pintype "passive"))
      (node (ref "R15") (pin "2") (pinfunction "2_2") (pintype "passive"))
    )
    (net (code "150") (name "unconnected-(ALT-Pad8)") (class "Default")
      (node (ref "ALT") (pin "8") (pinfunction "8_8") (pintype "passive"))
    )
    (net (code "151") (name "unconnected-(B1B-S-Pad2)") (class "Default")
      (node (ref "B1") (pin "2") (pinfunction "S_2") (pintype "passive"))
    )
    (net (code "152") (name "unconnected-(B2B-S-Pad2)") (class "Default")
      (node (ref "B2") (pin "2") (pinfunction "S_2") (pintype "passive"))
    )
    (net (code "153") (name "unconnected-(X9-Pad5)") (class "Default")
      (node (ref "X9") (pin "5") (pinfunction "5_5") (pintype "passive"))
    )
    (net (code "154") (name "unconnected-(X9-Pad6)") (class "Default")
      (node (ref "X9") (pin "6") (pinfunction "6_6") (pintype "passive"))
    )
    (net (code "155") (name "unconnected-(X9-Pad7)") (class "Default")
      (node (ref "X9") (pin "7") (pinfunction "7_7") (pintype "passive"))
    )
    (net (code "156") (name "unconnected-(X9-Pad8)") (class "Default")
      (node (ref "X9") (pin "8") (pinfunction "8_8") (pintype "passive"))
    )
    (net (code "157") (name "unconnected-(X9-Pad9)") (class "Default")
      (node (ref "X9") (pin "9") (pinfunction "9_9") (pintype "passive"))
    )
    (net (code "158") (name "unconnected-(X9-Pad10)") (class "Default")
      (node (ref "X9") (pin "10") (pinfunction "10_10") (pintype "passive"))
    )
    (net (code "159") (name "unconnected-(X9-Pad11)") (class "Default")
      (node (ref "X9") (pin "11") (pinfunction "11_11") (pintype "passive"))
    )
    (net (code "160") (name "unconnected-(X9-Pad12)") (class "Default")
      (node (ref "X9") (pin "12") (pinfunction "12_12") (pintype "passive"))
    )
    (net (code "161") (name "unconnected-(X9-Pad13)") (class "Default")
      (node (ref "X9") (pin "13") (pinfunction "13_13") (pintype "passive"))
    )
    (net (code "162") (name "unconnected-(X9-Pad14)") (class "Default")
      (node (ref "X9") (pin "14") (pinfunction "14_14") (pintype "passive"))
    )
    (net (code "163") (name "unconnected-(X9-Pad15)") (class "Default")
      (node (ref "X9") (pin "15") (pinfunction "15_15") (pintype "passive"))
    )
    (net (code "164") (name "unconnected-(X10-Pad5)") (class "Default")
      (node (ref "X10") (pin "5") (pinfunction "5_5") (pintype "passive"))
    )
    (net (code "165") (name "unconnected-(X10-Pad12)") (class "Default")
      (node (ref "X10") (pin "12") (pinfunction "12_12") (pintype "passive"))
    )
    (net (code "166") (name "unconnected-(X10-Pad13)") (class "Default")
      (node (ref "X10") (pin "13") (pinfunction "13_13") (pintype "passive"))
    )
    (net (code "167") (name "unconnected-(X10-Pad14)") (class "Default")
      (node (ref "X10") (pin "14") (pinfunction "14_14") (pintype "passive"))
    )
    (net (code "168") (name "unconnected-(X10-Pad15)") (class "Default")
      (node (ref "X10") (pin "15") (pinfunction "15_15") (pintype "passive"))
    )
    (net (code "169") (name "unconnected-(X11-Pad7)") (class "Default")
      (node (ref "X11") (pin "7") (pinfunction "7_7") (pintype "passive"))
    )
  )
)
